# midi-servo.net
KiCad netlist of a schematic drawn in EAGLE
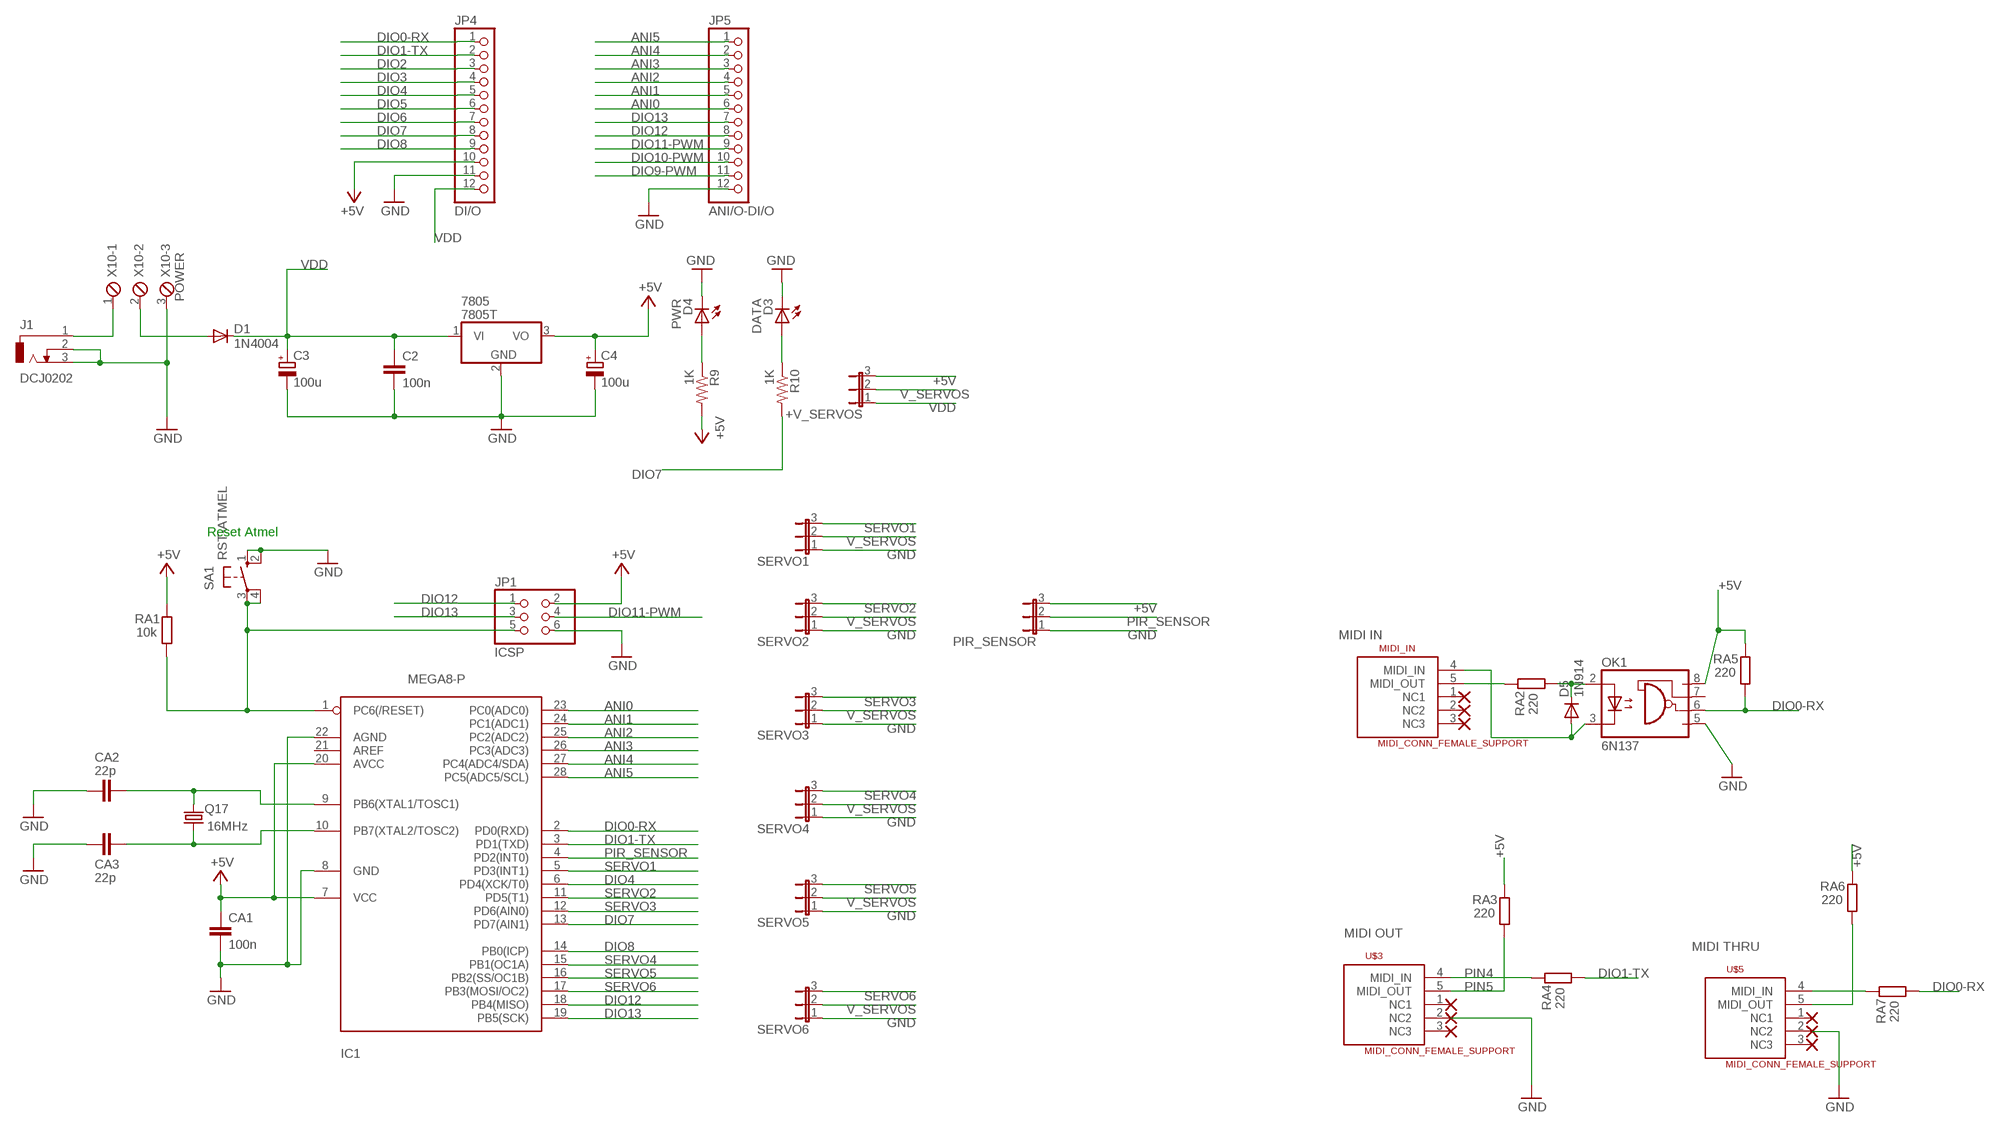
[diagram p0: schematic, sheet 1]

(export (version "E")
  (design (tool "Eeschema 10.0.6"))
  (components
    (comp (ref "+V_SERVOS")
      (value "JP2E")
      (footprint "eagle-import:JP2")
      (libsource (lib "eagle-import") (part "JP2E"))
    )
    (comp (ref "7805")
      (value "7805T")
      (footprint "eagle-import:TO220H")
      (libsource (lib "eagle-import") (part "78T05"))
    )
    (comp (ref "C2")
      (value "100n")
      (footprint "eagle-import:C050-025X075")
      (libsource (lib "eagle-import") (part "C-EU050-025X075"))
    )
    (comp (ref "C3")
      (value "100u")
      (footprint "eagle-import:E2,5-7")
      (libsource (lib "eagle-import") (part "CPOL-EUE2.5-7"))
    )
    (comp (ref "C4")
      (value "100u")
      (footprint "eagle-import:E2,5-7")
      (libsource (lib "eagle-import") (part "CPOL-EUE2.5-7"))
    )
    (comp (ref "CA1")
      (value "100n")
      (footprint "eagle-import:C050-025X075")
      (libsource (lib "eagle-import") (part "C-EU050-025X075"))
    )
    (comp (ref "CA2")
      (value "22p")
      (footprint "eagle-import:C050-025X075")
      (libsource (lib "eagle-import") (part "C-EU050-025X075"))
    )
    (comp (ref "CA3")
      (value "22p")
      (footprint "eagle-import:C050-025X075")
      (libsource (lib "eagle-import") (part "C-EU050-025X075"))
    )
    (comp (ref "D1")
      (value "1N4004")
      (footprint "eagle-import:DO41-10")
      (libsource (lib "eagle-import") (part "1N4004"))
    )
    (comp (ref "D3")
      (value "DATA")
      (footprint "eagle-import:LED4MM")
      (libsource (lib "eagle-import") (part "HLMP-M"))
    )
    (comp (ref "D4")
      (value "PWR")
      (footprint "eagle-import:LED4MM")
      (libsource (lib "eagle-import") (part "HLMP-M"))
    )
    (comp (ref "D5")
      (value "1N914")
      (footprint "eagle-import:DO34-7")
      (libsource (lib "eagle-import") (part "BAS15"))
    )
    (comp (ref "IC1")
      (value "MEGA8-P")
      (footprint "eagle-import:DIL28-3")
      (libsource (lib "eagle-import") (part "MEGA8-P"))
    )
    (comp (ref "J1")
      (value "DCJ0202")
      (footprint "eagle-import:DCJ0202")
      (libsource (lib "eagle-import") (part "DCJ0202"))
    )
    (comp (ref "JP1")
      (value "ICSP")
      (footprint "eagle-import:2X03")
      (libsource (lib "eagle-import") (part "PINHD-2X3"))
    )
    (comp (ref "JP4")
      (value "DI/O")
      (footprint "eagle-import:1X12")
      (libsource (lib "eagle-import") (part "PINHD-1X12"))
    )
    (comp (ref "JP5")
      (value "ANI/O-DI/O")
      (footprint "eagle-import:1X12")
      (libsource (lib "eagle-import") (part "PINHD-1X12"))
    )
    (comp (ref "MIDI_IN")
      (value "MIDI_CONN_FEMALE_SUPPORT")
      (footprint "eagle-import:DIN_5_FEMALE_SUPPORT")
      (libsource (lib "eagle-import") (part "MIDI_CONN_FEMALE_SUPPORT"))
    )
    (comp (ref "OK1")
      (value "6N137")
      (footprint "eagle-import:DIL08")
      (libsource (lib "eagle-import") (part "6N137"))
    )
    (comp (ref "PIR_SENSOR")
      (value "JP2E")
      (footprint "eagle-import:JP2")
      (libsource (lib "eagle-import") (part "JP2E"))
    )
    (comp (ref "Q17")
      (value "16MHz")
      (footprint "eagle-import:HC49_S")
      (libsource (lib "eagle-import") (part "CRYSTALHC49S"))
    )
    (comp (ref "R9")
      (value "1K")
      (footprint "eagle-import:0204_5")
      (libsource (lib "eagle-import") (part "R-US_0204/5"))
    )
    (comp (ref "R10")
      (value "1K")
      (footprint "eagle-import:0204_5")
      (libsource (lib "eagle-import") (part "R-US_0204/5"))
    )
    (comp (ref "RA1")
      (value "10k")
      (footprint "eagle-import:0204_5")
      (libsource (lib "eagle-import") (part "R-EU_0204/5"))
    )
    (comp (ref "RA2")
      (value "220")
      (footprint "eagle-import:0204_5")
      (libsource (lib "eagle-import") (part "R-EU_0204/5"))
    )
    (comp (ref "RA3")
      (value "220")
      (footprint "eagle-import:0204_5")
      (libsource (lib "eagle-import") (part "R-EU_0204/5"))
    )
    (comp (ref "RA4")
      (value "220")
      (footprint "eagle-import:0204_5")
      (libsource (lib "eagle-import") (part "R-EU_0204/5"))
    )
    (comp (ref "RA5")
      (value "220")
      (footprint "eagle-import:0204_5")
      (libsource (lib "eagle-import") (part "R-EU_0204/5"))
    )
    (comp (ref "RA6")
      (value "220")
      (footprint "eagle-import:0204_5")
      (libsource (lib "eagle-import") (part "R-EU_0204/5"))
    )
    (comp (ref "RA7")
      (value "220")
      (footprint "eagle-import:0204_5")
      (libsource (lib "eagle-import") (part "R-EU_0204/5"))
    )
    (comp (ref "SA1")
      (value "RST-ATMEL")
      (footprint "eagle-import:B3F-10XX")
      (libsource (lib "eagle-import") (part "10-XX"))
    )
    (comp (ref "SERVO1")
      (value "JP2E")
      (footprint "eagle-import:JP2")
      (libsource (lib "eagle-import") (part "JP2E"))
    )
    (comp (ref "SERVO2")
      (value "JP2E")
      (footprint "eagle-import:JP2")
      (libsource (lib "eagle-import") (part "JP2E"))
    )
    (comp (ref "SERVO3")
      (value "JP2E")
      (footprint "eagle-import:JP2")
      (libsource (lib "eagle-import") (part "JP2E"))
    )
    (comp (ref "SERVO4")
      (value "JP2E")
      (footprint "eagle-import:JP2")
      (libsource (lib "eagle-import") (part "JP2E"))
    )
    (comp (ref "SERVO5")
      (value "JP2E")
      (footprint "eagle-import:JP2")
      (libsource (lib "eagle-import") (part "JP2E"))
    )
    (comp (ref "SERVO6")
      (value "JP2E")
      (footprint "eagle-import:JP2")
      (libsource (lib "eagle-import") (part "JP2E"))
    )
    (comp (ref "U$3")
      (value "MIDI_CONN_FEMALE_SUPPORT")
      (footprint "eagle-import:DIN_5_FEMALE_SUPPORT")
      (libsource (lib "eagle-import") (part "MIDI_CONN_FEMALE_SUPPORT"))
    )
    (comp (ref "U$5")
      (value "MIDI_CONN_FEMALE_SUPPORT")
      (footprint "eagle-import:DIN_5_FEMALE_SUPPORT")
      (libsource (lib "eagle-import") (part "MIDI_CONN_FEMALE_SUPPORT"))
    )
    (comp (ref "X10")
      (value "POWER")
      (footprint "eagle-import:3POL254")
      (libsource (lib "eagle-import") (part "MPT3"))
    )
  )
  (nets
    (net (code "1") (name "+5V") (class "Default")
      (node (ref "+V_SERVOS") (pin "3") (pinfunction "3_3") (pintype "passive"))
      (node (ref "7805") (pin "3") (pinfunction "VO_3") (pintype "passive"))
      (node (ref "C4") (pin "+") (pinfunction "+_+") (pintype "passive"))
      (node (ref "CA1") (pin "1") (pinfunction "1_1") (pintype "passive"))
      (node (ref "IC1") (pin "20") (pinfunction "AVCC_20") (pintype "power_in"))
      (node (ref "IC1") (pin "7") (pinfunction "VCC_7") (pintype "power_in"))
      (node (ref "JP1") (pin "2") (pinfunction "2_2") (pintype "passive"))
      (node (ref "JP4") (pin "10") (pinfunction "10_10") (pintype "passive"))
      (node (ref "OK1") (pin "8") (pinfunction "VCC_8") (pintype "passive"))
      (node (ref "PIR_SENSOR") (pin "3") (pinfunction "3_3") (pintype "passive"))
      (node (ref "R9") (pin "2") (pinfunction "2_2") (pintype "passive"))
      (node (ref "RA1") (pin "1") (pinfunction "1_1") (pintype "passive"))
      (node (ref "RA3") (pin "1") (pinfunction "1_1") (pintype "passive"))
      (node (ref "RA5") (pin "1") (pinfunction "1_1") (pintype "passive"))
      (node (ref "RA6") (pin "1") (pinfunction "1_1") (pintype "passive"))
    )
    (net (code "2") (name "/ANI0") (class "Default")
      (node (ref "IC1") (pin "23") (pinfunction "PC0(ADC0)_23") (pintype "bidirectional"))
      (node (ref "JP5") (pin "6") (pinfunction "6_6") (pintype "passive"))
    )
    (net (code "3") (name "/ANI1") (class "Default")
      (node (ref "IC1") (pin "24") (pinfunction "PC1(ADC1)_24") (pintype "bidirectional"))
      (node (ref "JP5") (pin "5") (pinfunction "5_5") (pintype "passive"))
    )
    (net (code "4") (name "/ANI2") (class "Default")
      (node (ref "IC1") (pin "25") (pinfunction "PC2(ADC2)_25") (pintype "bidirectional"))
      (node (ref "JP5") (pin "4") (pinfunction "4_4") (pintype "passive"))
    )
    (net (code "5") (name "/ANI3") (class "Default")
      (node (ref "IC1") (pin "26") (pinfunction "PC3(ADC3)_26") (pintype "bidirectional"))
      (node (ref "JP5") (pin "3") (pinfunction "3_3") (pintype "passive"))
    )
    (net (code "6") (name "/ANI4") (class "Default")
      (node (ref "IC1") (pin "27") (pinfunction "PC4(ADC4/SDA)_27") (pintype "bidirectional"))
      (node (ref "JP5") (pin "2") (pinfunction "2_2") (pintype "passive"))
    )
    (net (code "7") (name "/ANI5") (class "Default")
      (node (ref "IC1") (pin "28") (pinfunction "PC5(ADC5/SCL)_28") (pintype "bidirectional"))
      (node (ref "JP5") (pin "1") (pinfunction "1_1") (pintype "passive"))
    )
    (net (code "8") (name "/DIO0-RX") (class "Default")
      (node (ref "IC1") (pin "2") (pinfunction "PD0(RXD)_2") (pintype "bidirectional"))
      (node (ref "JP4") (pin "1") (pinfunction "1_1") (pintype "passive"))
      (node (ref "OK1") (pin "6") (pinfunction "VO_6") (pintype "passive"))
      (node (ref "RA5") (pin "2") (pinfunction "2_2") (pintype "passive"))
      (node (ref "RA7") (pin "2") (pinfunction "2_2") (pintype "passive"))
    )
    (net (code "9") (name "/DIO1-TX") (class "Default")
      (node (ref "IC1") (pin "3") (pinfunction "PD1(TXD)_3") (pintype "bidirectional"))
      (node (ref "JP4") (pin "2") (pinfunction "2_2") (pintype "passive"))
      (node (ref "RA4") (pin "2") (pinfunction "2_2") (pintype "passive"))
    )
    (net (code "10") (name "/DIO2") (class "Default")
      (node (ref "JP4") (pin "3") (pinfunction "3_3") (pintype "passive"))
    )
    (net (code "11") (name "/DIO3") (class "Default")
      (node (ref "JP4") (pin "4") (pinfunction "4_4") (pintype "passive"))
    )
    (net (code "12") (name "/DIO4") (class "Default")
      (node (ref "IC1") (pin "6") (pinfunction "PD4(XCK/T0)_6") (pintype "bidirectional"))
      (node (ref "JP4") (pin "5") (pinfunction "5_5") (pintype "passive"))
    )
    (net (code "13") (name "/DIO5") (class "Default")
      (node (ref "JP4") (pin "6") (pinfunction "6_6") (pintype "passive"))
    )
    (net (code "14") (name "/DIO6") (class "Default")
      (node (ref "JP4") (pin "7") (pinfunction "7_7") (pintype "passive"))
    )
    (net (code "15") (name "/DIO7") (class "Default")
      (node (ref "IC1") (pin "13") (pinfunction "PD7(AIN1)_13") (pintype "bidirectional"))
      (node (ref "JP4") (pin "8") (pinfunction "8_8") (pintype "passive"))
      (node (ref "R10") (pin "2") (pinfunction "2_2") (pintype "passive"))
    )
    (net (code "16") (name "/DIO8") (class "Default")
      (node (ref "IC1") (pin "14") (pinfunction "PB0(ICP)_14") (pintype "bidirectional"))
      (node (ref "JP4") (pin "9") (pinfunction "9_9") (pintype "passive"))
    )
    (net (code "17") (name "/DIO9-PWM") (class "Default")
      (node (ref "JP5") (pin "11") (pinfunction "11_11") (pintype "passive"))
    )
    (net (code "18") (name "/DIO10-PWM") (class "Default")
      (node (ref "JP5") (pin "10") (pinfunction "10_10") (pintype "passive"))
    )
    (net (code "19") (name "/DIO11-PWM") (class "Default")
      (node (ref "JP1") (pin "4") (pinfunction "4_4") (pintype "passive"))
      (node (ref "JP5") (pin "9") (pinfunction "9_9") (pintype "passive"))
    )
    (net (code "20") (name "/DIO12") (class "Default")
      (node (ref "IC1") (pin "18") (pinfunction "PB4(MISO)_18") (pintype "bidirectional"))
      (node (ref "JP1") (pin "1") (pinfunction "1_1") (pintype "passive"))
      (node (ref "JP5") (pin "8") (pinfunction "8_8") (pintype "passive"))
    )
    (net (code "21") (name "/DIO13") (class "Default")
      (node (ref "IC1") (pin "19") (pinfunction "PB5(SCK)_19") (pintype "bidirectional"))
      (node (ref "JP1") (pin "3") (pinfunction "3_3") (pintype "passive"))
      (node (ref "JP5") (pin "7") (pinfunction "7_7") (pintype "passive"))
    )
    (net (code "22") (name "/PIR_SENSOR") (class "Default")
      (node (ref "IC1") (pin "4") (pinfunction "PD2(INT0)_4") (pintype "bidirectional"))
      (node (ref "PIR_SENSOR") (pin "2") (pinfunction "2_2") (pintype "passive"))
    )
    (net (code "23") (name "/SERVO1") (class "Default")
      (node (ref "IC1") (pin "5") (pinfunction "PD3(INT1)_5") (pintype "bidirectional"))
      (node (ref "SERVO1") (pin "3") (pinfunction "3_3") (pintype "passive"))
    )
    (net (code "24") (name "/SERVO2") (class "Default")
      (node (ref "IC1") (pin "11") (pinfunction "PD5(T1)_11") (pintype "bidirectional"))
      (node (ref "SERVO2") (pin "3") (pinfunction "3_3") (pintype "passive"))
    )
    (net (code "25") (name "/SERVO3") (class "Default")
      (node (ref "IC1") (pin "12") (pinfunction "PD6(AIN0)_12") (pintype "bidirectional"))
      (node (ref "SERVO3") (pin "3") (pinfunction "3_3") (pintype "passive"))
    )
    (net (code "26") (name "/SERVO4") (class "Default")
      (node (ref "IC1") (pin "15") (pinfunction "PB1(OC1A)_15") (pintype "bidirectional"))
      (node (ref "SERVO4") (pin "3") (pinfunction "3_3") (pintype "passive"))
    )
    (net (code "27") (name "/SERVO5") (class "Default")
      (node (ref "IC1") (pin "16") (pinfunction "PB2(SS/OC1B)_16") (pintype "bidirectional"))
      (node (ref "SERVO5") (pin "3") (pinfunction "3_3") (pintype "passive"))
    )
    (net (code "28") (name "/SERVO6") (class "Default")
      (node (ref "IC1") (pin "17") (pinfunction "PB3(MOSI/OC2)_17") (pintype "bidirectional"))
      (node (ref "SERVO6") (pin "3") (pinfunction "3_3") (pintype "passive"))
    )
    (net (code "29") (name "/VDD") (class "Default")
      (node (ref "+V_SERVOS") (pin "1") (pinfunction "1_1") (pintype "passive"))
      (node (ref "7805") (pin "1") (pinfunction "VI_1") (pintype "input"))
      (node (ref "C2") (pin "1") (pinfunction "1_1") (pintype "passive"))
      (node (ref "C3") (pin "+") (pinfunction "+_+") (pintype "passive"))
      (node (ref "D1") (pin "C") (pinfunction "C_C") (pintype "passive"))
      (node (ref "JP4") (pin "12") (pinfunction "12_12") (pintype "passive"))
    )
    (net (code "30") (name "/V_SERVOS") (class "Default")
      (node (ref "+V_SERVOS") (pin "2") (pinfunction "2_2") (pintype "passive"))
      (node (ref "SERVO1") (pin "2") (pinfunction "2_2") (pintype "passive"))
      (node (ref "SERVO2") (pin "2") (pinfunction "2_2") (pintype "passive"))
      (node (ref "SERVO3") (pin "2") (pinfunction "2_2") (pintype "passive"))
      (node (ref "SERVO4") (pin "2") (pinfunction "2_2") (pintype "passive"))
      (node (ref "SERVO5") (pin "2") (pinfunction "2_2") (pintype "passive"))
      (node (ref "SERVO6") (pin "2") (pinfunction "2_2") (pintype "passive"))
    )
    (net (code "31") (name "GND") (class "Default")
      (node (ref "7805") (pin "2") (pinfunction "GND_2") (pintype "passive"))
      (node (ref "C2") (pin "2") (pinfunction "2_2") (pintype "passive"))
      (node (ref "C3") (pin "-") (pinfunction "-_-") (pintype "passive"))
      (node (ref "C4") (pin "-") (pinfunction "-_-") (pintype "passive"))
      (node (ref "CA1") (pin "2") (pinfunction "2_2") (pintype "passive"))
      (node (ref "CA2") (pin "2") (pinfunction "2_2") (pintype "passive"))
      (node (ref "CA3") (pin "2") (pinfunction "2_2") (pintype "passive"))
      (node (ref "D3") (pin "A") (pinfunction "C_A") (pintype "passive"))
      (node (ref "D4") (pin "A") (pinfunction "C_A") (pintype "passive"))
      (node (ref "IC1") (pin "22") (pinfunction "AGND_22") (pintype "power_in"))
      (node (ref "IC1") (pin "8") (pinfunction "GND_8") (pintype "power_in"))
      (node (ref "J1") (pin "2") (pinfunction "2_2") (pintype "passive"))
      (node (ref "J1") (pin "3") (pinfunction "3_3") (pintype "passive"))
      (node (ref "JP1") (pin "6") (pinfunction "6_6") (pintype "passive"))
      (node (ref "JP4") (pin "11") (pinfunction "11_11") (pintype "passive"))
      (node (ref "JP5") (pin "12") (pinfunction "12_12") (pintype "passive"))
      (node (ref "OK1") (pin "5") (pinfunction "GND_5") (pintype "passive"))
      (node (ref "PIR_SENSOR") (pin "1") (pinfunction "1_1") (pintype "passive"))
      (node (ref "SA1") (pin "1") (pinfunction "S_1") (pintype "passive"))
      (node (ref "SA1") (pin "2") (pinfunction "S1_2") (pintype "passive"))
      (node (ref "SERVO1") (pin "1") (pinfunction "1_1") (pintype "passive"))
      (node (ref "SERVO2") (pin "1") (pinfunction "1_1") (pintype "passive"))
      (node (ref "SERVO3") (pin "1") (pinfunction "1_1") (pintype "passive"))
      (node (ref "SERVO4") (pin "1") (pinfunction "1_1") (pintype "passive"))
      (node (ref "SERVO5") (pin "1") (pinfunction "1_1") (pintype "passive"))
      (node (ref "SERVO6") (pin "1") (pinfunction "1_1") (pintype "passive"))
      (node (ref "U$3") (pin "2") (pinfunction "NC2_2") (pintype "bidirectional"))
      (node (ref "U$5") (pin "2") (pinfunction "NC2_2") (pintype "bidirectional"))
      (node (ref "X10") (pin "3") (pinfunction "1_3") (pintype "passive"))
    )
    (net (code "32") (name "Net-(D3-A)") (class "Default")
      (node (ref "D3") (pin "K") (pinfunction "A_K") (pintype "passive"))
      (node (ref "R10") (pin "1") (pinfunction "1_1") (pintype "passive"))
    )
    (net (code "33") (name "Net-(D4-A)") (class "Default")
      (node (ref "D4") (pin "K") (pinfunction "A_K") (pintype "passive"))
      (node (ref "R9") (pin "1") (pinfunction "1_1") (pintype "passive"))
    )
    (net (code "34") (name "Net-(IC1-PB6(XTAL1{slash}TOSC1))") (class "Default")
      (node (ref "CA2") (pin "1") (pinfunction "1_1") (pintype "passive"))
      (node (ref "IC1") (pin "9") (pinfunction "PB6(XTAL1/TOSC1)_9") (pintype "bidirectional"))
      (node (ref "Q17") (pin "2") (pinfunction "2_2") (pintype "passive"))
    )
    (net (code "35") (name "Net-(IC1-PB7(XTAL2{slash}TOSC2))") (class "Default")
      (node (ref "CA3") (pin "1") (pinfunction "1_1") (pintype "passive"))
      (node (ref "IC1") (pin "10") (pinfunction "PB7(XTAL2/TOSC2)_10") (pintype "bidirectional"))
      (node (ref "Q17") (pin "1") (pinfunction "1_1") (pintype "passive"))
    )
    (net (code "36") (name "Net-(IC1-PC6({slash}RESET))") (class "Default")
      (node (ref "IC1") (pin "1") (pinfunction "PC6(/RESET)_1") (pintype "bidirectional"))
      (node (ref "JP1") (pin "5") (pinfunction "5_5") (pintype "passive"))
      (node (ref "RA1") (pin "2") (pinfunction "2_2") (pintype "passive"))
      (node (ref "SA1") (pin "3") (pinfunction "P_3") (pintype "passive"))
      (node (ref "SA1") (pin "4") (pinfunction "P1_4") (pintype "passive"))
    )
    (net (code "37") (name "Net-(J1-Pad1)") (class "Default")
      (node (ref "J1") (pin "1") (pinfunction "1_1") (pintype "passive"))
      (node (ref "X10") (pin "1") (pinfunction "1_1") (pintype "passive"))
    )
    (net (code "38") (name "Net-(MIDI_IN-MIDI_IN)") (class "Default")
      (node (ref "D5") (pin "A") (pinfunction "A_A") (pintype "passive"))
      (node (ref "MIDI_IN") (pin "4") (pinfunction "MIDI_IN_4") (pintype "bidirectional"))
      (node (ref "OK1") (pin "3") (pinfunction "C_3") (pintype "passive"))
    )
    (net (code "39") (name "Net-(MIDI_IN-MIDI_OUT)") (class "Default")
      (node (ref "MIDI_IN") (pin "5") (pinfunction "MIDI_OUT_5") (pintype "bidirectional"))
      (node (ref "RA2") (pin "1") (pinfunction "1_1") (pintype "passive"))
    )
    (net (code "40") (name "Net-(OK1-A)") (class "Default")
      (node (ref "D5") (pin "C") (pinfunction "C_C") (pintype "passive"))
      (node (ref "OK1") (pin "2") (pinfunction "A_2") (pintype "passive"))
      (node (ref "RA2") (pin "2") (pinfunction "2_2") (pintype "passive"))
    )
    (net (code "41") (name "Net-(U$3-MIDI_IN)") (class "Default")
      (node (ref "RA4") (pin "1") (pinfunction "1_1") (pintype "passive"))
      (node (ref "U$3") (pin "4") (pinfunction "MIDI_IN_4") (pintype "bidirectional"))
    )
    (net (code "42") (name "Net-(U$3-MIDI_OUT)") (class "Default")
      (node (ref "RA3") (pin "2") (pinfunction "2_2") (pintype "passive"))
      (node (ref "U$3") (pin "5") (pinfunction "MIDI_OUT_5") (pintype "bidirectional"))
    )
    (net (code "43") (name "Net-(U$5-MIDI_IN)") (class "Default")
      (node (ref "RA7") (pin "1") (pinfunction "1_1") (pintype "passive"))
      (node (ref "U$5") (pin "4") (pinfunction "MIDI_IN_4") (pintype "bidirectional"))
    )
    (net (code "44") (name "Net-(U$5-MIDI_OUT)") (class "Default")
      (node (ref "RA6") (pin "2") (pinfunction "2_2") (pintype "passive"))
      (node (ref "U$5") (pin "5") (pinfunction "MIDI_OUT_5") (pintype "bidirectional"))
    )
    (net (code "45") (name "Net-(X10B-1)") (class "Default")
      (node (ref "D1") (pin "A") (pinfunction "A_A") (pintype "passive"))
      (node (ref "X10") (pin "2") (pinfunction "1_2") (pintype "passive"))
    )
    (net (code "46") (name "unconnected-(IC1-AREF-Pad21)") (class "Default")
      (node (ref "IC1") (pin "21") (pinfunction "AREF_21") (pintype "passive"))
    )
    (net (code "47") (name "unconnected-(MIDI_IN-NC1-Pad1)") (class "Default")
      (node (ref "MIDI_IN") (pin "1") (pinfunction "NC1_1") (pintype "bidirectional"))
    )
    (net (code "48") (name "unconnected-(MIDI_IN-NC2-Pad2)") (class "Default")
      (node (ref "MIDI_IN") (pin "2") (pinfunction "NC2_2") (pintype "bidirectional"))
    )
    (net (code "49") (name "unconnected-(MIDI_IN-NC3-Pad3)") (class "Default")
      (node (ref "MIDI_IN") (pin "3") (pinfunction "NC3_3") (pintype "bidirectional"))
    )
    (net (code "50") (name "unconnected-(OK1-VE-Pad7)") (class "Default")
      (node (ref "OK1") (pin "7") (pinfunction "VE_7") (pintype "passive"))
    )
    (net (code "51") (name "unconnected-(U$3-NC1-Pad1)") (class "Default")
      (node (ref "U$3") (pin "1") (pinfunction "NC1_1") (pintype "bidirectional"))
    )
    (net (code "52") (name "unconnected-(U$3-NC3-Pad3)") (class "Default")
      (node (ref "U$3") (pin "3") (pinfunction "NC3_3") (pintype "bidirectional"))
    )
    (net (code "53") (name "unconnected-(U$5-NC1-Pad1)") (class "Default")
      (node (ref "U$5") (pin "1") (pinfunction "NC1_1") (pintype "bidirectional"))
    )
    (net (code "54") (name "unconnected-(U$5-NC3-Pad3)") (class "Default")
      (node (ref "U$5") (pin "3") (pinfunction "NC3_3") (pintype "bidirectional"))
    )
  )
)
